# Hopper.net
KiCad netlist of a schematic drawn in Altium Designer
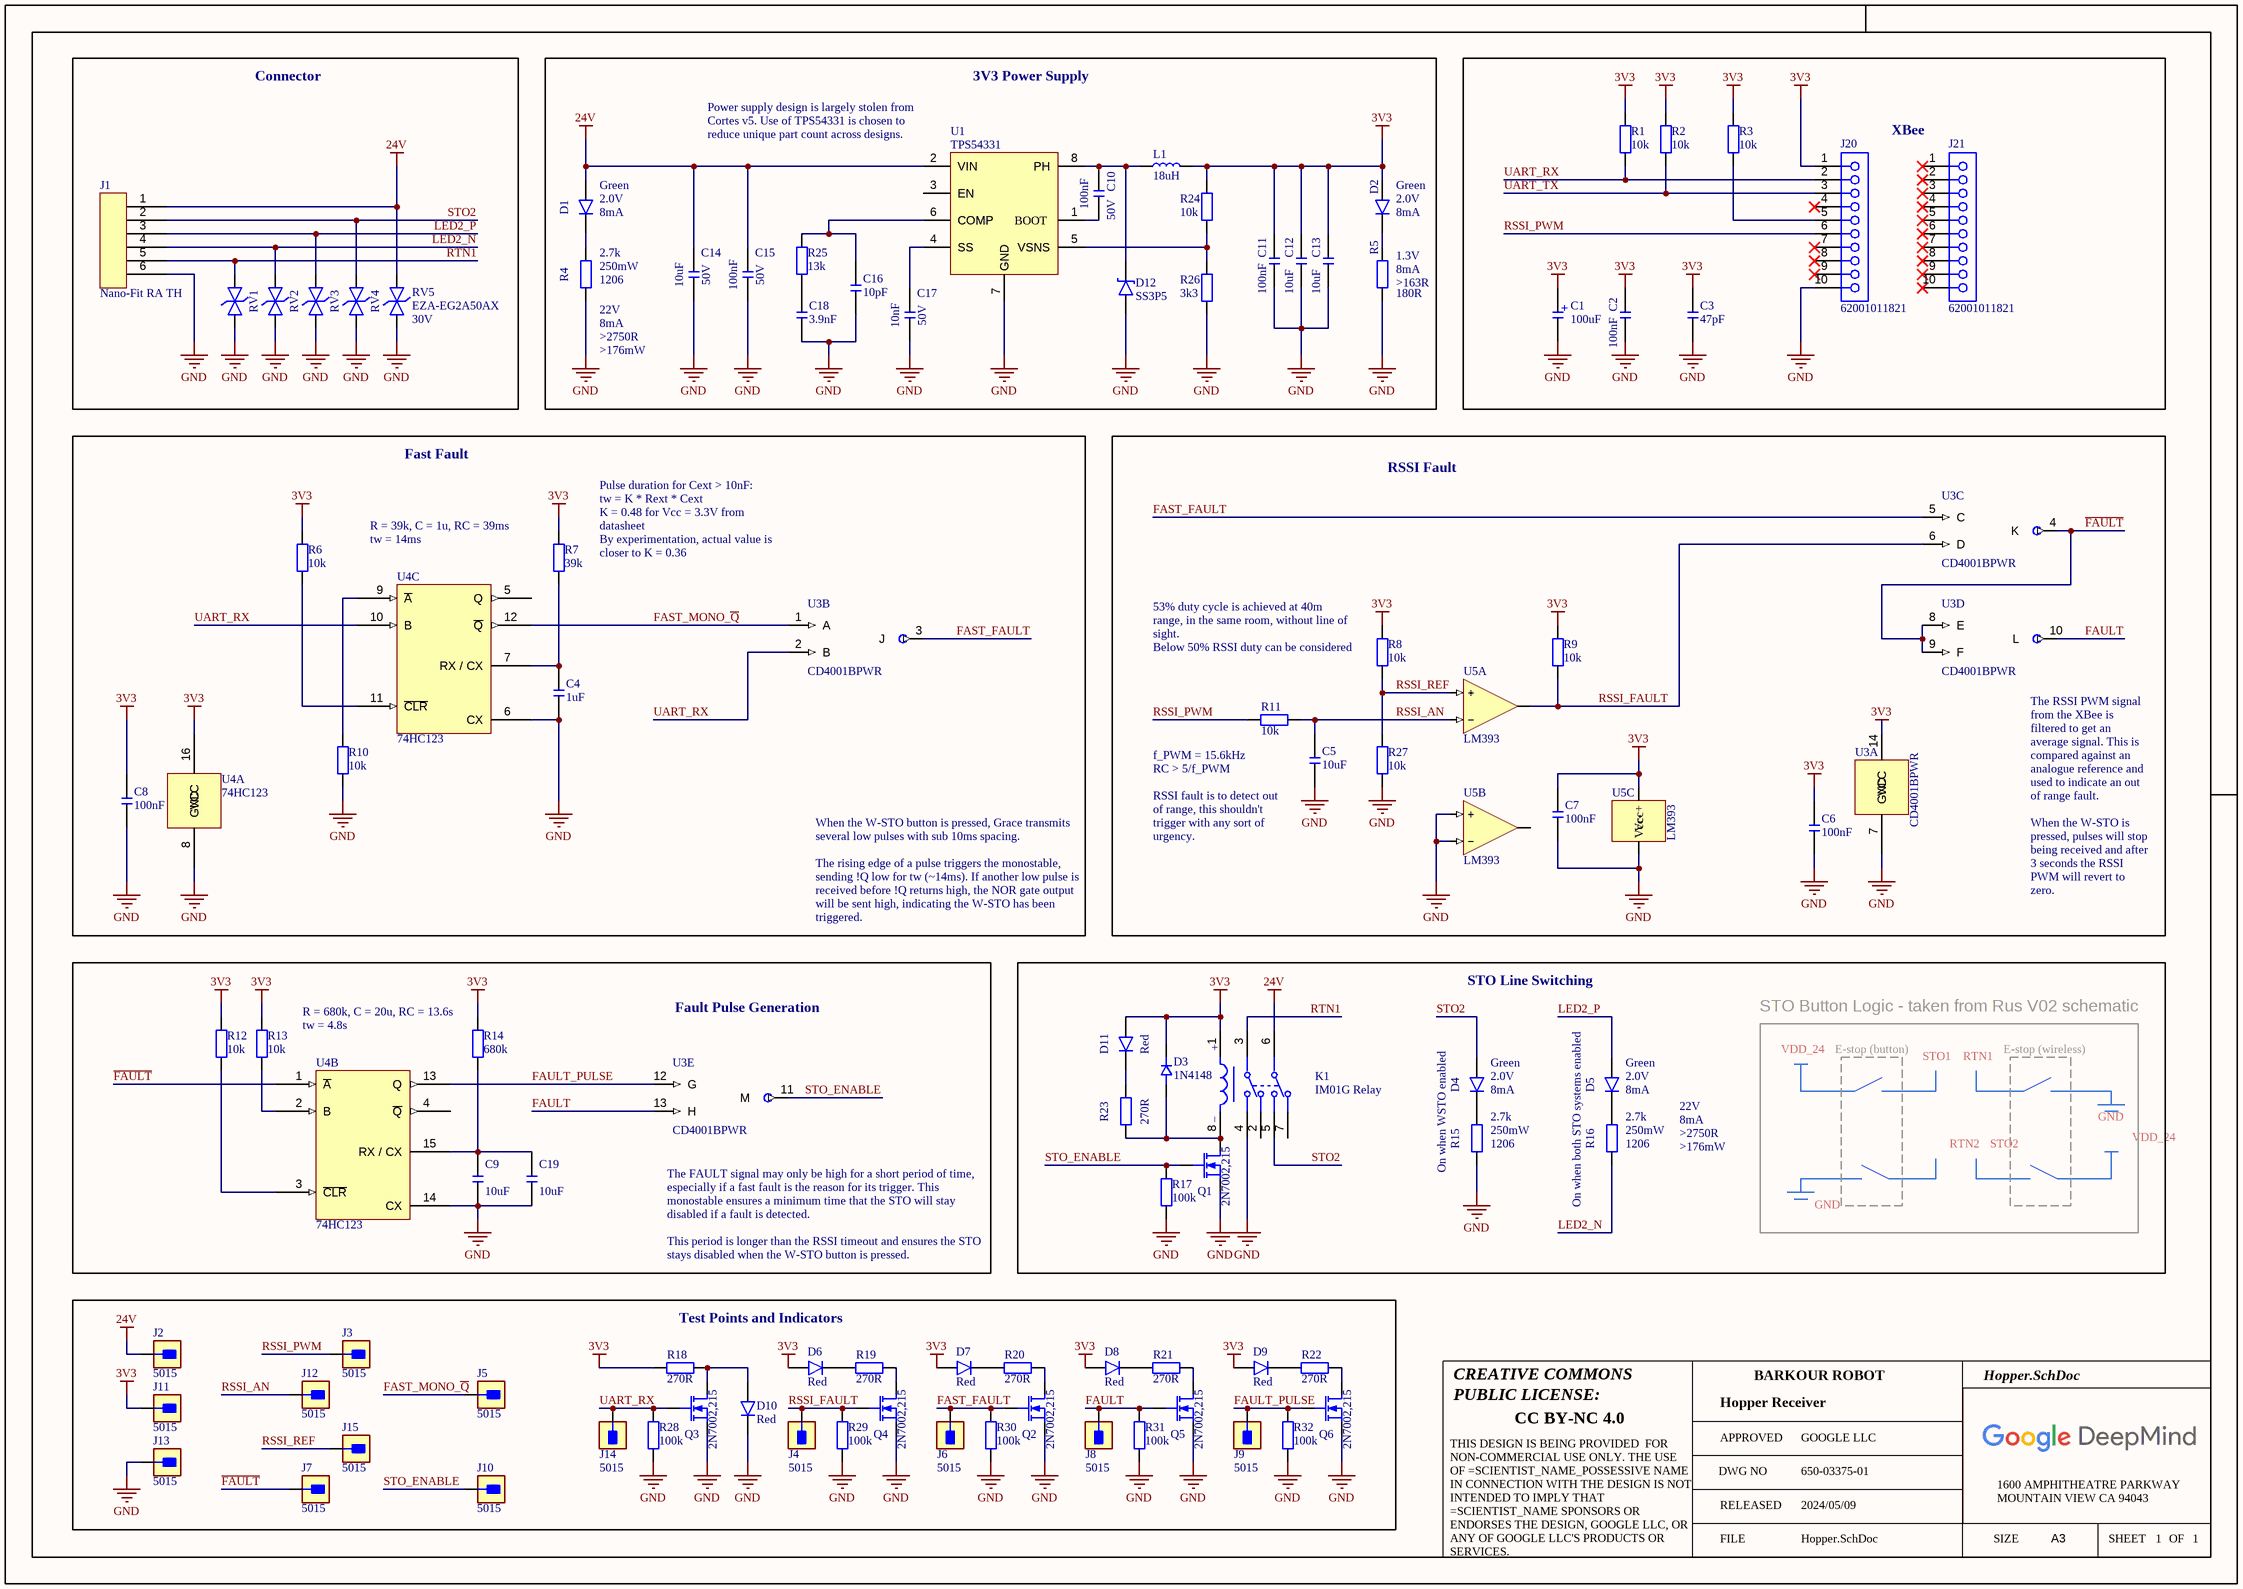
[diagram p0: Hopper.SchDoc]

(export (version "E")
  (design (tool "Eeschema 10.0.6"))
  (components
    (comp (ref "C1")
      (value "100uF")
      (footprint "CAP ALSMD ELEC 5.3MM H5.8MM")
      (description "Generic Polarised Capacitor")
      (fields (field (name "TOLERANCE") "20%"))
      (libsource (lib "DMR_common_lib") (part "C_POL"))
    )
    (comp (ref "C2")
      (value "100nF")
      (footprint "CAP 0402_1005 RF")
      (description "Generic Capacitor")
      (fields (field (name "TOLERANCE") "10%"))
      (libsource (lib "DMR_common_lib") (part "C"))
    )
    (comp (ref "C3")
      (value "47pF")
      (footprint "CAP 0603_1608 RF")
      (description "Capacitor")
      (fields (field (name "TOLERANCE") "20%"))
      (libsource (lib "DMR_common_lib") (part "C"))
    )
    (comp (ref "C4")
      (value "1uF")
      (footprint "CAP 0603_1608 RF")
      (description "Capacitor")
      (fields (field (name "TOLERANCE") "20%"))
      (libsource (lib "DMR_common_lib") (part "C"))
    )
    (comp (ref "C5")
      (value "10uF")
      (footprint "CAP 0603_1608 RF")
      (description "Capacitor")
      (fields (field (name "TOLERANCE") "10%"))
      (libsource (lib "DMR_common_lib") (part "C"))
    )
    (comp (ref "C6")
      (value "100nF")
      (footprint "CAP 0603_1608 RF")
      (description "Capacitor")
      (fields (field (name "TOLERANCE") "20%"))
      (libsource (lib "DMR_common_lib") (part "C"))
    )
    (comp (ref "C7")
      (value "100nF")
      (footprint "CAP 0603_1608 RF")
      (description "Capacitor")
      (fields (field (name "TOLERANCE") "20%"))
      (libsource (lib "DMR_common_lib") (part "C"))
    )
    (comp (ref "C8")
      (value "100nF")
      (footprint "CAP 0603_1608 RF")
      (description "Capacitor")
      (fields (field (name "TOLERANCE") "20%"))
      (libsource (lib "DMR_common_lib") (part "C"))
    )
    (comp (ref "C9")
      (value "10uF")
      (footprint "CAP 0402_1005")
      (description "Generic Capacitor")
      (fields (field (name "TOLERANCE") "20%"))
      (libsource (lib "DMR_common_lib") (part "C"))
    )
    (comp (ref "C10")
      (value "100nF")
      (footprint "CAP 0402_1005 RF")
      (description "Generic Capacitor")
      (fields (field (name "TOLERANCE") "10%") (field (name "VOLTAGE RATING") "50V"))
      (libsource (lib "DMR_common_lib") (part "C"))
    )
    (comp (ref "C11")
      (value "100nF")
      (footprint "CAP 0402_1005 RF")
      (description "Generic Capacitor")
      (fields (field (name "TOLERANCE") "10%"))
      (libsource (lib "DMR_common_lib") (part "C"))
    )
    (comp (ref "C12")
      (value "10uF")
      (footprint "CAP 0402_1005 RF")
      (description "Generic Capacitor")
      (fields (field (name "TOLERANCE") "20%"))
      (libsource (lib "DMR_common_lib") (part "C"))
    )
    (comp (ref "C13")
      (value "10uF")
      (footprint "CAP 0402_1005 RF")
      (description "Generic Capacitor")
      (fields (field (name "TOLERANCE") "20%"))
      (libsource (lib "DMR_common_lib") (part "C"))
    )
    (comp (ref "C14")
      (value "10uF")
      (footprint "CAP 1206_3216")
      (description "Generic Capacitor")
      (fields (field (name "TOLERANCE") "10%") (field (name "VOLTAGE RATING") "50V"))
      (libsource (lib "DMR_common_lib") (part "C"))
    )
    (comp (ref "C15")
      (value "100nF")
      (footprint "CAP 0402_1005 RF")
      (description "Generic Capacitor")
      (fields (field (name "TOLERANCE") "10%") (field (name "VOLTAGE RATING") "50V"))
      (libsource (lib "DMR_common_lib") (part "C"))
    )
    (comp (ref "C16")
      (value "10pF")
      (footprint "CAP 0402_1005 RF")
      (description "Generic Capacitor")
      (fields (field (name "TOLERANCE") "5%"))
      (libsource (lib "DMR_common_lib") (part "C"))
    )
    (comp (ref "C17")
      (value "10nF")
      (footprint "CAP 0402_1005 RF")
      (description "Generic Capacitor")
      (fields (field (name "TOLERANCE") "10%") (field (name "VOLTAGE RATING") "50V"))
      (libsource (lib "DMR_common_lib") (part "C"))
    )
    (comp (ref "C18")
      (value "3.9nF")
      (footprint "CAP 0402_1005 RF")
      (description "Generic Capacitor")
      (fields (field (name "TOLERANCE") "10%"))
      (libsource (lib "DMR_common_lib") (part "C"))
    )
    (comp (ref "C19")
      (value "10uF")
      (footprint "CAP 0402_1005")
      (description "Generic Capacitor")
      (fields (field (name "TOLERANCE") "20%"))
      (libsource (lib "DMR_common_lib") (part "C"))
    )
    (comp (ref "D1")
      (value "150040VS73240")
      (footprint "LED 0402_1005 GREEN")
      (description "Green SMD LED, 0402, 20mA Ic, 2V")
      (fields (field (name "FORWARD VOLTAGE") "2.0V") (field (name "COLOUR") "Green"))
      (libsource (lib "DMR_common_lib") (part "LED_GREEN_0402"))
    )
    (comp (ref "D2")
      (value "150040VS73240")
      (footprint "LED 0402_1005 GREEN")
      (description "Green SMD LED, 0402, 20mA Ic, 2V")
      (fields (field (name "FORWARD VOLTAGE") "2.0V") (field (name "COLOUR") "Green"))
      (libsource (lib "DMR_common_lib") (part "LED_GREEN_0402"))
    )
    (comp (ref "D3")
      (value "1N4148")
      (footprint "SOD323")
      (description "Signal Diode VR=75V IF=150mA Trr=4ns P=200mW")
      (fields
        (field (name "MANUFACTURER") "Diodes")
        (field (name "MANUFACTURER PART NUMBER") "1N4148WS-7-F")
        (field (name "COLLOQUIAL") "1N4148")
      )
      (libsource (lib "DMR_common_lib") (part "1N4148"))
    )
    (comp (ref "D4")
      (value "150040VS73240")
      (footprint "LED 0402_1005 GREEN")
      (description "Green SMD LED, 0402, 20mA Ic, 2V")
      (fields (field (name "FORWARD VOLTAGE") "2.0V") (field (name "COLOUR") "Green"))
      (libsource (lib "DMR_common_lib") (part "LED_GREEN_0402"))
    )
    (comp (ref "D5")
      (value "150040VS73240")
      (footprint "LED 0402_1005 GREEN")
      (description "Green SMD LED, 0402, 20mA Ic, 2V")
      (fields (field (name "FORWARD VOLTAGE") "2.0V") (field (name "COLOUR") "Green"))
      (libsource (lib "DMR_common_lib") (part "LED_GREEN_0402"))
    )
    (comp (ref "D6")
      (value "150040RS73240")
      (footprint "LED 0402_1005 RED")
      (description "Red SMD LED, 0402, 20mA Ic, 2V")
      (fields (field (name "COLOUR") "Red"))
      (libsource (lib "DMR_common_lib") (part "LED_RED_0402"))
    )
    (comp (ref "D7")
      (value "150040RS73240")
      (footprint "LED 0402_1005 RED")
      (description "Red SMD LED, 0402, 20mA Ic, 2V")
      (fields (field (name "COLOUR") "Red"))
      (libsource (lib "DMR_common_lib") (part "LED_RED_0402"))
    )
    (comp (ref "D8")
      (value "150040RS73240")
      (footprint "LED 0402_1005 RED")
      (description "Red SMD LED, 0402, 20mA Ic, 2V")
      (fields (field (name "COLOUR") "Red"))
      (libsource (lib "DMR_common_lib") (part "LED_RED_0402"))
    )
    (comp (ref "D9")
      (value "150040RS73240")
      (footprint "LED 0402_1005 RED")
      (description "Red SMD LED, 0402, 20mA Ic, 2V")
      (fields (field (name "COLOUR") "Red"))
      (libsource (lib "DMR_common_lib") (part "LED_RED_0402"))
    )
    (comp (ref "D10")
      (value "150040RS73240")
      (footprint "LED 0402_1005 RED")
      (description "Red SMD LED, 0402, 20mA Ic, 2V")
      (fields (field (name "COLOUR") "Red"))
      (libsource (lib "DMR_common_lib") (part "LED_RED_0402"))
    )
    (comp (ref "D11")
      (value "150040RS73240")
      (footprint "LED 0402_1005 RED")
      (description "Red SMD LED, 0402, 20mA Ic, 2V")
      (fields (field (name "COLOUR") "Red"))
      (libsource (lib "DMR_common_lib") (part "LED_RED_0402"))
    )
    (comp (ref "D12")
      (value "SS3P5-M3/84A")
      (footprint "DO-220AA")
      (description "VISHAY   SS3P5-M3/84A   DIODE, RECTIFIER, SCHOTTKY, 3A, 50V, SMP")
      (fields (field (name "MANUFACTURER") "Vishay") (field (name "COLLOQUIAL") "SS3P5"))
      (libsource (lib "DMR_common_lib") (part "SS3P5-M3/84A"))
    )
    (comp (ref "J1")
      (value "105314-1206")
      (footprint "MOLEX 1053141206")
      (description "Nano-Fit Right Angle Header; Through Hole; 2.50mm; Dual Row; 6 Circuit; Gold Plated")
      (fields (field (name "MANUFACTURER") "Molex") (field (name "COLLOQUIAL") "Nano-Fit RA TH"))
      (libsource (lib "DMR_common_lib") (part "Nano-Fit RA TH 6 Way Header Dual Row"))
    )
    (comp (ref "J2")
      (value "5015")
      (footprint "FP-5015-MFG-RF")
      (description "PC TEST POINT MINIATURE")
      (fields
        (field (name "MANUFACTURER") "keystone")
        (field (name "OCTOPART") "https://octopart.com/5015-keystone-3822")
      )
      (libsource (lib "") (part "5015_1"))
    )
    (comp (ref "J3")
      (value "5015")
      (footprint "FP-5015-MFG-RF")
      (description "PC TEST POINT MINIATURE")
      (fields
        (field (name "MANUFACTURER") "keystone")
        (field (name "OCTOPART") "https://octopart.com/5015-keystone-3822")
      )
      (libsource (lib "") (part "5015_1"))
    )
    (comp (ref "J4")
      (value "5015")
      (footprint "FP-5015-MFG-RF")
      (description "PC TEST POINT MINIATURE")
      (fields
        (field (name "MANUFACTURER") "keystone")
        (field (name "OCTOPART") "https://octopart.com/5015-keystone-3822")
      )
      (libsource (lib "DMR_common_lib") (part "5015"))
    )
    (comp (ref "J5")
      (value "5015")
      (footprint "FP-5015-MFG-RF")
      (description "PC TEST POINT MINIATURE")
      (fields
        (field (name "MANUFACTURER") "keystone")
        (field (name "OCTOPART") "https://octopart.com/5015-keystone-3822")
      )
      (libsource (lib "") (part "5015_1"))
    )
    (comp (ref "J6")
      (value "5015")
      (footprint "FP-5015-MFG-RF")
      (description "PC TEST POINT MINIATURE")
      (fields
        (field (name "MANUFACTURER") "keystone")
        (field (name "OCTOPART") "https://octopart.com/5015-keystone-3822")
      )
      (libsource (lib "DMR_common_lib") (part "5015"))
    )
    (comp (ref "J7")
      (value "5015")
      (footprint "FP-5015-MFG-RF")
      (description "PC TEST POINT MINIATURE")
      (fields
        (field (name "MANUFACTURER") "keystone")
        (field (name "OCTOPART") "https://octopart.com/5015-keystone-3822")
      )
      (libsource (lib "") (part "5015_1"))
    )
    (comp (ref "J8")
      (value "5015")
      (footprint "FP-5015-MFG-RF")
      (description "PC TEST POINT MINIATURE")
      (fields
        (field (name "MANUFACTURER") "keystone")
        (field (name "OCTOPART") "https://octopart.com/5015-keystone-3822")
      )
      (libsource (lib "DMR_common_lib") (part "5015"))
    )
    (comp (ref "J9")
      (value "5015")
      (footprint "FP-5015-MFG-RF")
      (description "PC TEST POINT MINIATURE")
      (fields
        (field (name "MANUFACTURER") "keystone")
        (field (name "OCTOPART") "https://octopart.com/5015-keystone-3822")
      )
      (libsource (lib "DMR_common_lib") (part "5015"))
    )
    (comp (ref "J10")
      (value "5015")
      (footprint "FP-5015-MFG-RF")
      (description "PC TEST POINT MINIATURE")
      (fields
        (field (name "MANUFACTURER") "keystone")
        (field (name "OCTOPART") "https://octopart.com/5015-keystone-3822")
      )
      (libsource (lib "") (part "5015_1"))
    )
    (comp (ref "J11")
      (value "5015")
      (footprint "FP-5015-MFG-RF")
      (description "PC TEST POINT MINIATURE")
      (fields
        (field (name "MANUFACTURER") "keystone")
        (field (name "OCTOPART") "https://octopart.com/5015-keystone-3822")
      )
      (libsource (lib "") (part "5015_1"))
    )
    (comp (ref "J12")
      (value "5015")
      (footprint "FP-5015-MFG-RF")
      (description "PC TEST POINT MINIATURE")
      (fields
        (field (name "MANUFACTURER") "keystone")
        (field (name "OCTOPART") "https://octopart.com/5015-keystone-3822")
      )
      (libsource (lib "") (part "5015_1"))
    )
    (comp (ref "J13")
      (value "5015")
      (footprint "FP-5015-MFG-RF")
      (description "PC TEST POINT MINIATURE")
      (fields
        (field (name "MANUFACTURER") "keystone")
        (field (name "OCTOPART") "https://octopart.com/5015-keystone-3822")
      )
      (libsource (lib "") (part "5015_1"))
    )
    (comp (ref "J14")
      (value "5015")
      (footprint "FP-5015-MFG-RF")
      (description "PC TEST POINT MINIATURE")
      (fields
        (field (name "MANUFACTURER") "keystone")
        (field (name "OCTOPART") "https://octopart.com/5015-keystone-3822")
      )
      (libsource (lib "DMR_common_lib") (part "5015"))
    )
    (comp (ref "J15")
      (value "5015")
      (footprint "FP-5015-MFG-RF")
      (description "PC TEST POINT MINIATURE")
      (fields
        (field (name "MANUFACTURER") "keystone")
        (field (name "OCTOPART") "https://octopart.com/5015-keystone-3822")
      )
      (libsource (lib "") (part "5015_1"))
    )
    (comp (ref "J20")
      (value "62001011821")
      (footprint "62001011821")
      (libsource (lib "Altium Content Vault") (part "Header_Female_1R_10P"))
    )
    (comp (ref "J21")
      (value "62001011821")
      (footprint "62001011821")
      (libsource (lib "Altium Content Vault") (part "Header_Female_1R_10P"))
    )
    (comp (ref "K1")
      (value "1462037-1")
      (footprint "TE IM Relay Gullwing")
      (description "Signal Relay 3VDC 2A DPDT (( 10mm 7.5mm 5.65mm)) Surface Mount Automotive")
      (fields
        (field (name "MANUFACTURER") "TE Connectivity Axicom")
        (field (name "COLLOQUIAL") "IM01G Relay")
      )
      (libsource (lib "DMR_common_lib") (part "IM01G"))
    )
    (comp (ref "L1")
      (value "SRR1050A-180Y")
      (footprint "INDUCTOR SMD SHIELDED 10x10mm")
      (description "Inductor Power Shielded Wirewound 18uH 30% 100KHz Ferrite 3.1A 0.051Ohm DCR Automotive T/R")
      (fields (field (name "MANUFACTURER") "Bourns") (field (name "INDUCTANCE") "18uH"))
      (libsource (lib "DMR_common_lib") (part "SRR1050A-180Y"))
    )
    (comp (ref "Q1")
      (value "2N7002,215")
      (footprint "NEXPERIA SOT-23-3")
      (description "MOSFET N-CH 60V 300MA SOT-23")
      (fields (field (name "MANUFACTURER") "Nexperia"))
      (libsource (lib "DMR_common_lib") (part "2N7002"))
    )
    (comp (ref "Q2")
      (value "2N7002,215")
      (footprint "NEXPERIA SOT-23-3")
      (description "MOSFET N-CH 60V 300MA SOT-23")
      (fields (field (name "MANUFACTURER") "Nexperia"))
      (libsource (lib "DMR_common_lib") (part "2N7002"))
    )
    (comp (ref "Q3")
      (value "2N7002,215")
      (footprint "NEXPERIA SOT-23-3")
      (description "MOSFET N-CH 60V 300MA SOT-23")
      (fields (field (name "MANUFACTURER") "Nexperia"))
      (libsource (lib "DMR_common_lib") (part "2N7002"))
    )
    (comp (ref "Q4")
      (value "2N7002,215")
      (footprint "NEXPERIA SOT-23-3")
      (description "MOSFET N-CH 60V 300MA SOT-23")
      (fields (field (name "MANUFACTURER") "Nexperia"))
      (libsource (lib "DMR_common_lib") (part "2N7002"))
    )
    (comp (ref "Q5")
      (value "2N7002,215")
      (footprint "NEXPERIA SOT-23-3")
      (description "MOSFET N-CH 60V 300MA SOT-23")
      (fields (field (name "MANUFACTURER") "Nexperia"))
      (libsource (lib "DMR_common_lib") (part "2N7002"))
    )
    (comp (ref "Q6")
      (value "2N7002,215")
      (footprint "NEXPERIA SOT-23-3")
      (description "MOSFET N-CH 60V 300MA SOT-23")
      (fields (field (name "MANUFACTURER") "Nexperia"))
      (libsource (lib "DMR_common_lib") (part "2N7002"))
    )
    (comp (ref "R1")
      (value "10k")
      (footprint "RES 0402_1005 RF")
      (description "Generic Resistor")
      (fields (field (name "TOLERANCE") "1%"))
      (libsource (lib "") (part "R_1"))
    )
    (comp (ref "R2")
      (value "10k")
      (footprint "RES 0402_1005 RF")
      (description "Generic Resistor")
      (fields (field (name "TOLERANCE") "1%"))
      (libsource (lib "") (part "R_1"))
    )
    (comp (ref "R3")
      (value "10k")
      (footprint "RES 0402_1005 RF")
      (description "Generic Resistor")
      (fields (field (name "TOLERANCE") "1%"))
      (libsource (lib "") (part "R_1"))
    )
    (comp (ref "R4")
      (value "2.7k")
      (footprint "RES 1206_3216 RF")
      (description "Resistor")
      (fields
        (field (name "SIZE CODE") "1206")
        (field (name "TOLERANCE") "1%")
        (field (name "POWER RATING") "250mW")
      )
      (libsource (lib "") (part "R_1"))
    )
    (comp (ref "R5")
      (value "180R")
      (footprint "RES 0402_1005 RF")
      (description "Generic Resistor")
      (fields (field (name "TOLERANCE") "1%"))
      (libsource (lib "") (part "R_1"))
    )
    (comp (ref "R6")
      (value "10k")
      (footprint "RES 0402_1005 RF")
      (description "Generic Resistor")
      (fields (field (name "TOLERANCE") "1%"))
      (libsource (lib "") (part "R_1"))
    )
    (comp (ref "R7")
      (value "39k")
      (footprint "RES 0603_1608 RF")
      (description "Resistor")
      (fields (field (name "TOLERANCE") "1%"))
      (libsource (lib "") (part "R_1"))
    )
    (comp (ref "R8")
      (value "10k")
      (footprint "RES 0402_1005 RF")
      (description "Generic Resistor")
      (fields (field (name "TOLERANCE") "1%"))
      (libsource (lib "") (part "R_1"))
    )
    (comp (ref "R9")
      (value "10k")
      (footprint "RES 0402_1005 RF")
      (description "Generic Resistor")
      (fields (field (name "TOLERANCE") "1%"))
      (libsource (lib "") (part "R_1"))
    )
    (comp (ref "R10")
      (value "10k")
      (footprint "RES 0402_1005 RF")
      (description "Generic Resistor")
      (fields (field (name "TOLERANCE") "1%"))
      (libsource (lib "") (part "R_1"))
    )
    (comp (ref "R11")
      (value "10k")
      (footprint "RES 0402_1005 RF")
      (description "Generic Resistor")
      (fields (field (name "TOLERANCE") "1%"))
      (libsource (lib "") (part "R_2"))
    )
    (comp (ref "R12")
      (value "10k")
      (footprint "RES 0402_1005 RF")
      (description "Generic Resistor")
      (fields (field (name "TOLERANCE") "1%"))
      (libsource (lib "") (part "R_1"))
    )
    (comp (ref "R13")
      (value "10k")
      (footprint "RES 0402_1005 RF")
      (description "Generic Resistor")
      (fields (field (name "TOLERANCE") "1%"))
      (libsource (lib "") (part "R_1"))
    )
    (comp (ref "R14")
      (value "680k")
      (footprint "RES 0603_1608 RF")
      (description "Resistor")
      (fields (field (name "TOLERANCE") "1%"))
      (libsource (lib "") (part "R_1"))
    )
    (comp (ref "R15")
      (value "2.7k")
      (footprint "RES 1206_3216 RF")
      (description "Resistor")
      (fields
        (field (name "SIZE CODE") "1206")
        (field (name "TOLERANCE") "1%")
        (field (name "POWER RATING") "250mW")
      )
      (libsource (lib "") (part "R_1"))
    )
    (comp (ref "R16")
      (value "2.7k")
      (footprint "RES 1206_3216 RF")
      (description "Resistor")
      (fields
        (field (name "SIZE CODE") "1206")
        (field (name "TOLERANCE") "1%")
        (field (name "POWER RATING") "250mW")
      )
      (libsource (lib "") (part "R_1"))
    )
    (comp (ref "R17")
      (value "100k")
      (footprint "RES 0402_1005 RF")
      (description "Generic Resistor")
      (fields (field (name "TOLERANCE") "1%"))
      (libsource (lib "") (part "R_1"))
    )
    (comp (ref "R18")
      (value "270R")
      (footprint "RES 0402_1005 RF")
      (description "Generic Resistor")
      (fields (field (name "TOLERANCE") "1%"))
      (libsource (lib "DMR_common_lib") (part "R"))
    )
    (comp (ref "R19")
      (value "270R")
      (footprint "RES 0402_1005 RF")
      (description "Generic Resistor")
      (fields (field (name "TOLERANCE") "1%"))
      (libsource (lib "DMR_common_lib") (part "R"))
    )
    (comp (ref "R20")
      (value "270R")
      (footprint "RES 0402_1005 RF")
      (description "Generic Resistor")
      (fields (field (name "TOLERANCE") "1%"))
      (libsource (lib "DMR_common_lib") (part "R"))
    )
    (comp (ref "R21")
      (value "270R")
      (footprint "RES 0402_1005 RF")
      (description "Generic Resistor")
      (fields (field (name "TOLERANCE") "1%"))
      (libsource (lib "DMR_common_lib") (part "R"))
    )
    (comp (ref "R22")
      (value "270R")
      (footprint "RES 0402_1005 RF")
      (description "Generic Resistor")
      (fields (field (name "TOLERANCE") "1%"))
      (libsource (lib "DMR_common_lib") (part "R"))
    )
    (comp (ref "R23")
      (value "270R")
      (footprint "RES 0402_1005 RF")
      (description "Generic Resistor")
      (fields (field (name "TOLERANCE") "1%"))
      (libsource (lib "") (part "R_1"))
    )
    (comp (ref "R24")
      (value "10k")
      (footprint "RES 0402_1005 RF")
      (description "Generic Resistor")
      (fields (field (name "TOLERANCE") "1%"))
      (libsource (lib "") (part "R_1"))
    )
    (comp (ref "R25")
      (value "13k")
      (footprint "RES 0402_1005 RF")
      (description "Generic Resistor")
      (fields (field (name "TOLERANCE") "1%"))
      (libsource (lib "") (part "R_1"))
    )
    (comp (ref "R26")
      (value "3k3")
      (footprint "RES 0402_1005 RF")
      (description "Generic Resistor")
      (fields (field (name "TOLERANCE") "1%"))
      (libsource (lib "") (part "R_1"))
    )
    (comp (ref "R27")
      (value "10k")
      (footprint "RES 0402_1005 RF")
      (description "Generic Resistor")
      (fields (field (name "TOLERANCE") "1%"))
      (libsource (lib "") (part "R_1"))
    )
    (comp (ref "R28")
      (value "100k")
      (footprint "RES 0402_1005 RF")
      (description "Generic Resistor")
      (fields (field (name "TOLERANCE") "1%"))
      (libsource (lib "") (part "R_1"))
    )
    (comp (ref "R29")
      (value "100k")
      (footprint "RES 0402_1005 RF")
      (description "Generic Resistor")
      (fields (field (name "TOLERANCE") "1%"))
      (libsource (lib "") (part "R_1"))
    )
    (comp (ref "R30")
      (value "100k")
      (footprint "RES 0402_1005 RF")
      (description "Generic Resistor")
      (fields (field (name "TOLERANCE") "1%"))
      (libsource (lib "") (part "R_1"))
    )
    (comp (ref "R31")
      (value "100k")
      (footprint "RES 0402_1005 RF")
      (description "Generic Resistor")
      (fields (field (name "TOLERANCE") "1%"))
      (libsource (lib "") (part "R_1"))
    )
    (comp (ref "R32")
      (value "100k")
      (footprint "RES 0402_1005 RF")
      (description "Generic Resistor")
      (fields (field (name "TOLERANCE") "1%"))
      (libsource (lib "") (part "R_1"))
    )
    (comp (ref "RV1")
      (value "EZA-EG2A50AX")
      (footprint "RES 0402_1005")
      (description "EZAEG Series 100 Vcl 0.05 pF 0402 Surface Mount ESD Suppressor")
      (fields (field (name "MANUFACTURER") "Panasonic"))
      (libsource (lib "DMR_common_lib") (part "EZA-EG2A50AX"))
    )
    (comp (ref "RV2")
      (value "EZA-EG2A50AX")
      (footprint "RES 0402_1005")
      (description "EZAEG Series 100 Vcl 0.05 pF 0402 Surface Mount ESD Suppressor")
      (fields (field (name "MANUFACTURER") "Panasonic"))
      (libsource (lib "DMR_common_lib") (part "EZA-EG2A50AX"))
    )
    (comp (ref "RV3")
      (value "EZA-EG2A50AX")
      (footprint "RES 0402_1005")
      (description "EZAEG Series 100 Vcl 0.05 pF 0402 Surface Mount ESD Suppressor")
      (fields (field (name "MANUFACTURER") "Panasonic"))
      (libsource (lib "DMR_common_lib") (part "EZA-EG2A50AX"))
    )
    (comp (ref "RV4")
      (value "EZA-EG2A50AX")
      (footprint "RES 0402_1005")
      (description "EZAEG Series 100 Vcl 0.05 pF 0402 Surface Mount ESD Suppressor")
      (fields (field (name "MANUFACTURER") "Panasonic"))
      (libsource (lib "DMR_common_lib") (part "EZA-EG2A50AX"))
    )
    (comp (ref "RV5")
      (value "EZA-EG2A50AX")
      (footprint "RES 0402_1005")
      (description "EZAEG Series 100 Vcl 0.05 pF 0402 Surface Mount ESD Suppressor")
      (fields (field (name "MANUFACTURER") "Panasonic") (field (name "OPERATING SUPPLY VOLTAGE") "30V"))
      (libsource (lib "DMR_common_lib") (part "EZA-EG2A50AX"))
    )
    (comp (ref "U1")
      (value "TPS54331GDR")
      (footprint "TI SOIC-8 D0008A")
      (description "3.5V to 28V Input, 3A, 570kHz Step-Down Converter with Eco-mode 8-SOIC -40 to 150")
      (fields (field (name "MANUFACTURER") "Texas Instruments") (field (name "COLLOQUIAL") "TPS54331"))
      (libsource (lib "DMR_common_lib") (part "TPS54331GDR"))
    )
    (comp (ref "U3")
      (value "CD4001BPWR")
      (footprint "TI TSSOP-14 PW")
      (description "4-ch, 2-input, 3-V to 18-V NOR gates 14-TSSOP -55 to 125")
      (fields (field (name "MANUFACTURER") "Texas Instruments"))
      (libsource (lib "DMR_common_lib") (part "CD4001BPWR"))
    )
    (comp (ref "U4")
      (value "CD74HC123PW")
      (footprint "TI TSSOP-16 PW")
      (description "High Speed CMOS Logic Dual etriggerable Monostable Multivibrators with eset 16-TSSOP -55 to 125")
      (fields (field (name "COLLOQUIAL") "74HC123"))
      (libsource (lib "DMR_common_lib") (part "74HC123"))
    )
    (comp (ref "U5")
      (value "LM393PT")
      (footprint "ST TSSOP-8")
      (description "Comparator Dual 18V/36V 8-Pin TSSOP T/R")
      (fields (field (name "MANUFACTURER") "ST") (field (name "COLLOQUIAL") "LM393"))
      (libsource (lib "DMR_common_lib") (part "LM393"))
    )
  )
  (nets
    (net (code "1") (name "/FAST_FAULT") (class "Default")
      (node (ref "J6") (pin "1") (pinfunction "1_1") (pintype "passive"))
      (node (ref "Q2") (pin "1") (pinfunction "G_1") (pintype "passive"))
      (node (ref "R30") (pin "2") (pinfunction "2_2") (pintype "passive"))
      (node (ref "U3") (pin "3") (pinfunction "J_3") (pintype "output"))
      (node (ref "U3") (pin "5") (pinfunction "C_5") (pintype "input"))
    )
    (net (code "2") (name "/FAST_MONO_~{Q}") (class "Default")
      (node (ref "J5") (pin "1") (pinfunction "1_1") (pintype "passive"))
      (node (ref "U3") (pin "1") (pinfunction "A_1") (pintype "input"))
      (node (ref "U4") (pin "12") (pinfunction "~{Q}_12") (pintype "output"))
    )
    (net (code "3") (name "/FAULT") (class "Default")
      (node (ref "J8") (pin "1") (pinfunction "1_1") (pintype "passive"))
      (node (ref "Q5") (pin "1") (pinfunction "G_1") (pintype "passive"))
      (node (ref "R31") (pin "2") (pinfunction "2_2") (pintype "passive"))
      (node (ref "U3") (pin "10") (pinfunction "L_10") (pintype "output"))
      (node (ref "U3") (pin "13") (pinfunction "H_13") (pintype "input"))
    )
    (net (code "4") (name "/FAULT_PULSE") (class "Default")
      (node (ref "J9") (pin "1") (pinfunction "1_1") (pintype "passive"))
      (node (ref "Q6") (pin "1") (pinfunction "G_1") (pintype "passive"))
      (node (ref "R32") (pin "2") (pinfunction "2_2") (pintype "passive"))
      (node (ref "U3") (pin "12") (pinfunction "G_12") (pintype "input"))
      (node (ref "U4") (pin "13") (pinfunction "Q_13") (pintype "output"))
    )
    (net (code "5") (name "/LED2_N") (class "Default")
      (node (ref "J1") (pin "4") (pintype "passive"))
      (node (ref "R16") (pin "1") (pinfunction "1_1") (pintype "passive"))
      (node (ref "RV2") (pin "2") (pinfunction "2_2") (pintype "passive"))
    )
    (net (code "6") (name "/LED2_P") (class "Default")
      (node (ref "D5") (pin "1") (pinfunction "+_1") (pintype "passive"))
      (node (ref "J1") (pin "3") (pintype "passive"))
      (node (ref "RV3") (pin "2") (pinfunction "2_2") (pintype "passive"))
    )
    (net (code "7") (name "/RSSI_AN") (class "Default")
      (node (ref "C5") (pin "2") (pinfunction "2_2") (pintype "passive"))
      (node (ref "J12") (pin "1") (pinfunction "1_1") (pintype "passive"))
      (node (ref "R11") (pin "2") (pinfunction "2_2") (pintype "passive"))
      (node (ref "U5") (pin "2") (pinfunction "−_2") (pintype "input"))
    )
    (net (code "8") (name "/RSSI_FAULT") (class "Default")
      (node (ref "J4") (pin "1") (pinfunction "1_1") (pintype "passive"))
      (node (ref "Q4") (pin "1") (pinfunction "G_1") (pintype "passive"))
      (node (ref "R29") (pin "2") (pinfunction "2_2") (pintype "passive"))
      (node (ref "R9") (pin "1") (pinfunction "1_1") (pintype "passive"))
      (node (ref "U3") (pin "6") (pinfunction "D_6") (pintype "input"))
      (node (ref "U5") (pin "1") (pinfunction "Out1_1") (pintype "open_collector"))
    )
    (net (code "9") (name "/RSSI_PWM") (class "Default")
      (node (ref "J20") (pin "6") (pinfunction "6_6") (pintype "passive"))
      (node (ref "J3") (pin "1") (pinfunction "1_1") (pintype "passive"))
      (node (ref "R11") (pin "1") (pinfunction "1_1") (pintype "passive"))
    )
    (net (code "10") (name "/RSSI_REF") (class "Default")
      (node (ref "J15") (pin "1") (pinfunction "1_1") (pintype "passive"))
      (node (ref "R27") (pin "2") (pinfunction "2_2") (pintype "passive"))
      (node (ref "R8") (pin "1") (pinfunction "1_1") (pintype "passive"))
      (node (ref "U5") (pin "3") (pinfunction "+_3") (pintype "input"))
    )
    (net (code "11") (name "/RTN1") (class "Default")
      (node (ref "J1") (pin "5") (pintype "passive"))
      (node (ref "K1") (pin "3") (pinfunction "3_3") (pintype "passive"))
      (node (ref "RV1") (pin "2") (pinfunction "2_2") (pintype "passive"))
    )
    (net (code "12") (name "/STO2") (class "Default")
      (node (ref "D4") (pin "1") (pinfunction "+_1") (pintype "passive"))
      (node (ref "J1") (pin "2") (pintype "passive"))
      (node (ref "K1") (pin "5") (pinfunction "5_5") (pintype "passive"))
      (node (ref "RV4") (pin "2") (pinfunction "2_2") (pintype "passive"))
    )
    (net (code "13") (name "/STO_ENABLE") (class "Default")
      (node (ref "J10") (pin "1") (pinfunction "1_1") (pintype "passive"))
      (node (ref "Q1") (pin "1") (pinfunction "G_1") (pintype "passive"))
      (node (ref "R17") (pin "2") (pinfunction "2_2") (pintype "passive"))
      (node (ref "U3") (pin "11") (pinfunction "M_11") (pintype "output"))
    )
    (net (code "14") (name "/UART_RX") (class "Default")
      (node (ref "J14") (pin "1") (pinfunction "1_1") (pintype "passive"))
      (node (ref "J20") (pin "2") (pinfunction "2_2") (pintype "passive"))
      (node (ref "Q3") (pin "1") (pinfunction "G_1") (pintype "passive"))
      (node (ref "R1") (pin "1") (pinfunction "1_1") (pintype "passive"))
      (node (ref "R28") (pin "2") (pinfunction "2_2") (pintype "passive"))
      (node (ref "U3") (pin "2") (pinfunction "B_2") (pintype "input"))
      (node (ref "U4") (pin "10") (pinfunction "B_10") (pintype "input"))
    )
    (net (code "15") (name "/UART_TX") (class "Default")
      (node (ref "J20") (pin "3") (pinfunction "3_3") (pintype "passive"))
      (node (ref "R2") (pin "1") (pinfunction "1_1") (pintype "passive"))
    )
    (net (code "16") (name "/~{FAULT}") (class "Default")
      (node (ref "J7") (pin "1") (pinfunction "1_1") (pintype "passive"))
      (node (ref "U3") (pin "4") (pinfunction "K_4") (pintype "output"))
      (node (ref "U3") (pin "8") (pinfunction "E_8") (pintype "input"))
      (node (ref "U3") (pin "9") (pinfunction "F_9") (pintype "input"))
      (node (ref "U4") (pin "1") (pinfunction "~{A}_1") (pintype "input"))
    )
    (net (code "17") (name "3V3") (class "Default")
      (node (ref "C1") (pin "1") (pinfunction "1_1") (pintype "passive"))
      (node (ref "C11") (pin "2") (pinfunction "2_2") (pintype "passive"))
      (node (ref "C12") (pin "2") (pinfunction "2_2") (pintype "passive"))
      (node (ref "C13") (pin "2") (pinfunction "2_2") (pintype "passive"))
      (node (ref "C2") (pin "2") (pinfunction "2_2") (pintype "passive"))
      (node (ref "C3") (pin "2") (pinfunction "2_2") (pintype "passive"))
      (node (ref "C6") (pin "2") (pinfunction "2_2") (pintype "passive"))
      (node (ref "C7") (pin "2") (pinfunction "2_2") (pintype "passive"))
      (node (ref "C8") (pin "2") (pinfunction "2_2") (pintype "passive"))
      (node (ref "D11") (pin "1") (pinfunction "+_1") (pintype "passive"))
      (node (ref "D2") (pin "1") (pinfunction "+_1") (pintype "passive"))
      (node (ref "D3") (pin "2") (pinfunction "2_2") (pintype "passive"))
      (node (ref "D6") (pin "1") (pinfunction "+_1") (pintype "passive"))
      (node (ref "D7") (pin "1") (pinfunction "+_1") (pintype "passive"))
      (node (ref "D8") (pin "1") (pinfunction "+_1") (pintype "passive"))
      (node (ref "D9") (pin "1") (pinfunction "+_1") (pintype "passive"))
      (node (ref "J11") (pin "1") (pinfunction "1_1") (pintype "passive"))
      (node (ref "J20") (pin "1") (pinfunction "1_1") (pintype "passive"))
      (node (ref "K1") (pin "1") (pinfunction "1_1") (pintype "passive"))
      (node (ref "L1") (pin "2") (pinfunction "2_2") (pintype "passive"))
      (node (ref "R1") (pin "2") (pinfunction "2_2") (pintype "passive"))
      (node (ref "R12") (pin "2") (pinfunction "2_2") (pintype "passive"))
      (node (ref "R13") (pin "2") (pinfunction "2_2") (pintype "passive"))
      (node (ref "R14") (pin "2") (pinfunction "2_2") (pintype "passive"))
      (node (ref "R18") (pin "2") (pinfunction "2_2") (pintype "passive"))
      (node (ref "R2") (pin "2") (pinfunction "2_2") (pintype "passive"))
      (node (ref "R24") (pin "2") (pinfunction "2_2") (pintype "passive"))
      (node (ref "R3") (pin "2") (pinfunction "2_2") (pintype "passive"))
      (node (ref "R6") (pin "2") (pinfunction "2_2") (pintype "passive"))
      (node (ref "R7") (pin "2") (pinfunction "2_2") (pintype "passive"))
      (node (ref "R8") (pin "2") (pinfunction "2_2") (pintype "passive"))
      (node (ref "R9") (pin "2") (pinfunction "2_2") (pintype "passive"))
      (node (ref "U3") (pin "14") (pinfunction "VCC_14") (pintype "power_in"))
      (node (ref "U4") (pin "16") (pinfunction "VCC_16") (pintype "power_in"))
      (node (ref "U5") (pin "8") (pinfunction "Vcc+_8") (pintype "power_in"))
    )
    (net (code "18") (name "24V") (class "Default")
      (node (ref "C14") (pin "2") (pinfunction "2_2") (pintype "passive"))
      (node (ref "C15") (pin "2") (pinfunction "2_2") (pintype "passive"))
      (node (ref "D1") (pin "1") (pinfunction "+_1") (pintype "passive"))
      (node (ref "J1") (pin "1") (pintype "passive"))
      (node (ref "J2") (pin "1") (pinfunction "1_1") (pintype "passive"))
      (node (ref "K1") (pin "6") (pinfunction "6_6") (pintype "passive"))
      (node (ref "RV5") (pin "2") (pinfunction "2_2") (pintype "passive"))
      (node (ref "U1") (pin "2") (pinfunction "VIN_2") (pintype "power_in"))
    )
    (net (code "19") (name "GND") (class "Default")
      (node (ref "C1") (pin "2") (pinfunction "2_2") (pintype "passive"))
      (node (ref "C11") (pin "1") (pinfunction "1_1") (pintype "passive"))
      (node (ref "C12") (pin "1") (pinfunction "1_1") (pintype "passive"))
      (node (ref "C13") (pin "1") (pinfunction "1_1") (pintype "passive"))
      (node (ref "C14") (pin "1") (pinfunction "1_1") (pintype "passive"))
      (node (ref "C15") (pin "1") (pinfunction "1_1") (pintype "passive"))
      (node (ref "C16") (pin "2") (pinfunction "2_2") (pintype "passive"))
      (node (ref "C17") (pin "1") (pinfunction "1_1") (pintype "passive"))
      (node (ref "C18") (pin "1") (pinfunction "1_1") (pintype "passive"))
      (node (ref "C19") (pin "1") (pinfunction "1_1") (pintype "passive"))
      (node (ref "C2") (pin "1") (pinfunction "1_1") (pintype "passive"))
      (node (ref "C3") (pin "1") (pinfunction "1_1") (pintype "passive"))
      (node (ref "C4") (pin "1") (pinfunction "1_1") (pintype "passive"))
      (node (ref "C5") (pin "1") (pinfunction "1_1") (pintype "passive"))
      (node (ref "C6") (pin "1") (pinfunction "1_1") (pintype "passive"))
      (node (ref "C7") (pin "1") (pinfunction "1_1") (pintype "passive"))
      (node (ref "C8") (pin "1") (pinfunction "1_1") (pintype "passive"))
      (node (ref "C9") (pin "1") (pinfunction "1_1") (pintype "passive"))
      (node (ref "D10") (pin "2") (pinfunction "-_2") (pintype "passive"))
      (node (ref "D12") (pin "1") (pinfunction "A_1") (pintype "passive"))
      (node (ref "J1") (pin "6") (pintype "passive"))
      (node (ref "J13") (pin "1") (pinfunction "1_1") (pintype "passive"))
      (node (ref "J20") (pin "10") (pinfunction "10_10") (pintype "passive"))
      (node (ref "K1") (pin "4") (pinfunction "4_4") (pintype "passive"))
      (node (ref "Q1") (pin "2") (pinfunction "S_2") (pintype "passive"))
      (node (ref "Q2") (pin "2") (pinfunction "S_2") (pintype "passive"))
      (node (ref "Q3") (pin "2") (pinfunction "S_2") (pintype "passive"))
      (node (ref "Q4") (pin "2") (pinfunction "S_2") (pintype "passive"))
      (node (ref "Q5") (pin "2") (pinfunction "S_2") (pintype "passive"))
      (node (ref "Q6") (pin "2") (pinfunction "S_2") (pintype "passive"))
      (node (ref "R10") (pin "1") (pinfunction "1_1") (pintype "passive"))
      (node (ref "R15") (pin "1") (pinfunction "1_1") (pintype "passive"))
      (node (ref "R17") (pin "1") (pinfunction "1_1") (pintype "passive"))
      (node (ref "R26") (pin "1") (pinfunction "1_1") (pintype "passive"))
      (node (ref "R27") (pin "1") (pinfunction "1_1") (pintype "passive"))
      (node (ref "R28") (pin "1") (pinfunction "1_1") (pintype "passive"))
      (node (ref "R29") (pin "1") (pinfunction "1_1") (pintype "passive"))
      (node (ref "R30") (pin "1") (pinfunction "1_1") (pintype "passive"))
      (node (ref "R31") (pin "1") (pinfunction "1_1") (pintype "passive"))
      (node (ref "R32") (pin "1") (pinfunction "1_1") (pintype "passive"))
      (node (ref "R4") (pin "1") (pinfunction "1_1") (pintype "passive"))
      (node (ref "R5") (pin "1") (pinfunction "1_1") (pintype "passive"))
      (node (ref "RV1") (pin "1") (pinfunction "1_1") (pintype "passive"))
      (node (ref "RV2") (pin "1") (pinfunction "1_1") (pintype "passive"))
      (node (ref "RV3") (pin "1") (pinfunction "1_1") (pintype "passive"))
      (node (ref "RV4") (pin "1") (pinfunction "1_1") (pintype "passive"))
      (node (ref "RV5") (pin "1") (pinfunction "1_1") (pintype "passive"))
      (node (ref "U1") (pin "7") (pinfunction "GND_7") (pintype "power_in"))
      (node (ref "U3") (pin "7") (pinfunction "GND_7") (pintype "power_in"))
      (node (ref "U4") (pin "14") (pinfunction "CX_14") (pintype "passive"))
      (node (ref "U4") (pin "6") (pinfunction "CX_6") (pintype "passive"))
      (node (ref "U4") (pin "8") (pinfunction "GND_8") (pintype "power_in"))
      (node (ref "U5") (pin "4") (pinfunction "Vcc-_4") (pintype "power_in"))
      (node (ref "U5") (pin "5") (pinfunction "+_5") (pintype "input"))
      (node (ref "U5") (pin "6") (pinfunction "−_6") (pintype "input"))
    )
    (net (code "20") (name "Net-(C18-Pad2)") (class "Default")
      (node (ref "C18") (pin "2") (pinfunction "2_2") (pintype "passive"))
      (node (ref "R25") (pin "1") (pinfunction "1_1") (pintype "passive"))
    )
    (net (code "21") (name "Net-(D1--)") (class "Default")
      (node (ref "D1") (pin "2") (pinfunction "-_2") (pintype "passive"))
      (node (ref "R4") (pin "2") (pinfunction "2_2") (pintype "passive"))
    )
    (net (code "22") (name "Net-(D2--)") (class "Default")
      (node (ref "D2") (pin "2") (pinfunction "-_2") (pintype "passive"))
      (node (ref "R5") (pin "2") (pinfunction "2_2") (pintype "passive"))
    )
    (net (code "23") (name "Net-(D4--)") (class "Default")
      (node (ref "D4") (pin "2") (pinfunction "-_2") (pintype "passive"))
      (node (ref "R15") (pin "2") (pinfunction "2_2") (pintype "passive"))
    )
    (net (code "24") (name "Net-(D5--)") (class "Default")
      (node (ref "D5") (pin "2") (pinfunction "-_2") (pintype "passive"))
      (node (ref "R16") (pin "2") (pinfunction "2_2") (pintype "passive"))
    )
    (net (code "25") (name "Net-(D6--)") (class "Default")
      (node (ref "D6") (pin "2") (pinfunction "-_2") (pintype "passive"))
      (node (ref "R19") (pin "2") (pinfunction "2_2") (pintype "passive"))
    )
    (net (code "26") (name "Net-(D7--)") (class "Default")
      (node (ref "D7") (pin "2") (pinfunction "-_2") (pintype "passive"))
      (node (ref "R20") (pin "2") (pinfunction "2_2") (pintype "passive"))
    )
    (net (code "27") (name "Net-(D8--)") (class "Default")
      (node (ref "D8") (pin "2") (pinfunction "-_2") (pintype "passive"))
      (node (ref "R21") (pin "2") (pinfunction "2_2") (pintype "passive"))
    )
    (net (code "28") (name "Net-(D9--)") (class "Default")
      (node (ref "D9") (pin "2") (pinfunction "-_2") (pintype "passive"))
      (node (ref "R22") (pin "2") (pinfunction "2_2") (pintype "passive"))
    )
    (net (code "29") (name "Net-(D10-+)") (class "Default")
      (node (ref "D10") (pin "1") (pinfunction "+_1") (pintype "passive"))
      (node (ref "Q3") (pin "3") (pinfunction "D_3") (pintype "passive"))
      (node (ref "R18") (pin "1") (pinfunction "1_1") (pintype "passive"))
    )
    (net (code "30") (name "Net-(D11--)") (class "Default")
      (node (ref "D11") (pin "2") (pinfunction "-_2") (pintype "passive"))
      (node (ref "R23") (pin "2") (pinfunction "2_2") (pintype "passive"))
    )
    (net (code "31") (name "Net-(D12-K)") (class "Default")
      (node (ref "C10") (pin "2") (pinfunction "2_2") (pintype "passive"))
      (node (ref "D12") (pin "2") (pinfunction "K_2") (pintype "passive"))
      (node (ref "L1") (pin "1") (pinfunction "1_1") (pintype "passive"))
      (node (ref "U1") (pin "8") (pinfunction "PH_8") (pintype "power_in"))
    )
    (net (code "32") (name "Net-(J20-Pad5)") (class "Default")
      (node (ref "J20") (pin "5") (pinfunction "5_5") (pintype "passive"))
      (node (ref "R3") (pin "1") (pinfunction "1_1") (pintype "passive"))
    )
    (net (code "33") (name "Net-(Q1-D)") (class "Default")
      (node (ref "D3") (pin "1") (pinfunction "1_1") (pintype "passive"))
      (node (ref "K1") (pin "8") (pinfunction "8_8") (pintype "passive"))
      (node (ref "Q1") (pin "3") (pinfunction "D_3") (pintype "passive"))
      (node (ref "R23") (pin "1") (pinfunction "1_1") (pintype "passive"))
    )
    (net (code "34") (name "Net-(Q2-D)") (class "Default")
      (node (ref "Q2") (pin "3") (pinfunction "D_3") (pintype "passive"))
      (node (ref "R20") (pin "1") (pinfunction "1_1") (pintype "passive"))
    )
    (net (code "35") (name "Net-(Q4-D)") (class "Default")
      (node (ref "Q4") (pin "3") (pinfunction "D_3") (pintype "passive"))
      (node (ref "R19") (pin "1") (pinfunction "1_1") (pintype "passive"))
    )
    (net (code "36") (name "Net-(Q5-D)") (class "Default")
      (node (ref "Q5") (pin "3") (pinfunction "D_3") (pintype "passive"))
      (node (ref "R21") (pin "1") (pinfunction "1_1") (pintype "passive"))
    )
    (net (code "37") (name "Net-(Q6-D)") (class "Default")
      (node (ref "Q6") (pin "3") (pinfunction "D_3") (pintype "passive"))
      (node (ref "R22") (pin "1") (pinfunction "1_1") (pintype "passive"))
    )
    (net (code "38") (name "Net-(U1-BOOT)") (class "Default")
      (node (ref "C10") (pin "1") (pinfunction "1_1") (pintype "passive"))
      (node (ref "U1") (pin "1") (pinfunction "BOOT_1") (pintype "passive"))
    )
    (net (code "39") (name "Net-(U1-COMP)") (class "Default")
      (node (ref "C16") (pin "1") (pinfunction "1_1") (pintype "passive"))
      (node (ref "R25") (pin "2") (pinfunction "2_2") (pintype "passive"))
      (node (ref "U1") (pin "6") (pinfunction "COMP_6") (pintype "passive"))
    )
    (net (code "40") (name "Net-(U1-SS)") (class "Default")
      (node (ref "C17") (pin "2") (pinfunction "2_2") (pintype "passive"))
      (node (ref "U1") (pin "4") (pinfunction "SS_4") (pintype "passive"))
    )
    (net (code "41") (name "Net-(U1-VSNS)") (class "Default")
      (node (ref "R24") (pin "1") (pinfunction "1_1") (pintype "passive"))
      (node (ref "R26") (pin "2") (pinfunction "2_2") (pintype "passive"))
      (node (ref "U1") (pin "5") (pinfunction "VSNS_5") (pintype "tri_state"))
    )
    (net (code "42") (name "Net-(U4B-B)") (class "Default")
      (node (ref "R13") (pin "1") (pinfunction "1_1") (pintype "passive"))
      (node (ref "U4") (pin "2") (pinfunction "B_2") (pintype "input"))
    )
    (net (code "43") (name "Net-(U4B-RX_{slash}_CX)") (class "Default")
      (node (ref "C19") (pin "2") (pinfunction "2_2") (pintype "passive"))
      (node (ref "C9") (pin "2") (pinfunction "2_2") (pintype "passive"))
      (node (ref "R14") (pin "1") (pinfunction "1_1") (pintype "passive"))
      (node (ref "U4") (pin "15") (pinfunction "RX_/_CX_15") (pintype "passive"))
    )
    (net (code "44") (name "Net-(U4B-~{CLR})") (class "Default")
      (node (ref "R12") (pin "1") (pinfunction "1_1") (pintype "passive"))
      (node (ref "U4") (pin "3") (pinfunction "~{CLR}_3") (pintype "input"))
    )
    (net (code "45") (name "Net-(U4C-RX_{slash}_CX)") (class "Default")
      (node (ref "C4") (pin "2") (pinfunction "2_2") (pintype "passive"))
      (node (ref "R7") (pin "1") (pinfunction "1_1") (pintype "passive"))
      (node (ref "U4") (pin "7") (pinfunction "RX_/_CX_7") (pintype "passive"))
    )
    (net (code "46") (name "Net-(U4C-~{A})") (class "Default")
      (node (ref "R10") (pin "2") (pinfunction "2_2") (pintype "passive"))
      (node (ref "U4") (pin "9") (pinfunction "~{A}_9") (pintype "input"))
    )
    (net (code "47") (name "Net-(U4C-~{CLR})") (class "Default")
      (node (ref "R6") (pin "1") (pinfunction "1_1") (pintype "passive"))
      (node (ref "U4") (pin "11") (pinfunction "~{CLR}_11") (pintype "input"))
    )
    (net (code "48") (name "unconnected-(J20-Pad4)") (class "Default")
      (node (ref "J20") (pin "4") (pinfunction "4_4") (pintype "passive+no_connect"))
    )
    (net (code "49") (name "unconnected-(J20-Pad7)") (class "Default")
      (node (ref "J20") (pin "7") (pinfunction "7_7") (pintype "passive+no_connect"))
    )
    (net (code "50") (name "unconnected-(J20-Pad8)") (class "Default")
      (node (ref "J20") (pin "8") (pinfunction "8_8") (pintype "passive+no_connect"))
    )
    (net (code "51") (name "unconnected-(J20-Pad9)") (class "Default")
      (node (ref "J20") (pin "9") (pinfunction "9_9") (pintype "passive+no_connect"))
    )
    (net (code "52") (name "unconnected-(J21-Pad1)") (class "Default")
      (node (ref "J21") (pin "1") (pinfunction "1_1") (pintype "passive+no_connect"))
    )
    (net (code "53") (name "unconnected-(J21-Pad2)") (class "Default")
      (node (ref "J21") (pin "2") (pinfunction "2_2") (pintype "passive+no_connect"))
    )
    (net (code "54") (name "unconnected-(J21-Pad3)") (class "Default")
      (node (ref "J21") (pin "3") (pinfunction "3_3") (pintype "passive+no_connect"))
    )
    (net (code "55") (name "unconnected-(J21-Pad4)") (class "Default")
      (node (ref "J21") (pin "4") (pinfunction "4_4") (pintype "passive+no_connect"))
    )
    (net (code "56") (name "unconnected-(J21-Pad5)") (class "Default")
      (node (ref "J21") (pin "5") (pinfunction "5_5") (pintype "passive+no_connect"))
    )
    (net (code "57") (name "unconnected-(J21-Pad6)") (class "Default")
      (node (ref "J21") (pin "6") (pinfunction "6_6") (pintype "passive+no_connect"))
    )
    (net (code "58") (name "unconnected-(J21-Pad7)") (class "Default")
      (node (ref "J21") (pin "7") (pinfunction "7_7") (pintype "passive+no_connect"))
    )
    (net (code "59") (name "unconnected-(J21-Pad8)") (class "Default")
      (node (ref "J21") (pin "8") (pinfunction "8_8") (pintype "passive+no_connect"))
    )
    (net (code "60") (name "unconnected-(J21-Pad9)") (class "Default")
      (node (ref "J21") (pin "9") (pinfunction "9_9") (pintype "passive+no_connect"))
    )
    (net (code "61") (name "unconnected-(J21-Pad10)") (class "Default")
      (node (ref "J21") (pin "10") (pinfunction "10_10") (pintype "passive+no_connect"))
    )
    (net (code "62") (name "unconnected-(K1-Pad2)") (class "Default")
      (node (ref "K1") (pin "2") (pinfunction "2_2") (pintype "passive"))
    )
    (net (code "63") (name "unconnected-(K1-Pad7)") (class "Default")
      (node (ref "K1") (pin "7") (pinfunction "7_7") (pintype "passive"))
    )
    (net (code "64") (name "unconnected-(U1-EN-Pad3)") (class "Default")
      (node (ref "U1") (pin "3") (pinfunction "EN_3") (pintype "passive"))
    )
    (net (code "65") (name "unconnected-(U4B-~{Q}-Pad4)") (class "Default")
      (node (ref "U4") (pin "4") (pinfunction "~{Q}_4") (pintype "output"))
    )
    (net (code "66") (name "unconnected-(U4C-Q-Pad5)") (class "Default")
      (node (ref "U4") (pin "5") (pinfunction "Q_5") (pintype "output"))
    )
    (net (code "67") (name "unconnected-(U5B-Out1-Pad7)") (class "Default")
      (node (ref "U5") (pin "7") (pinfunction "Out1_7") (pintype "open_collector"))
    )
  )
)
